# ESPF.net
KiCad netlist of a schematic drawn in EAGLE
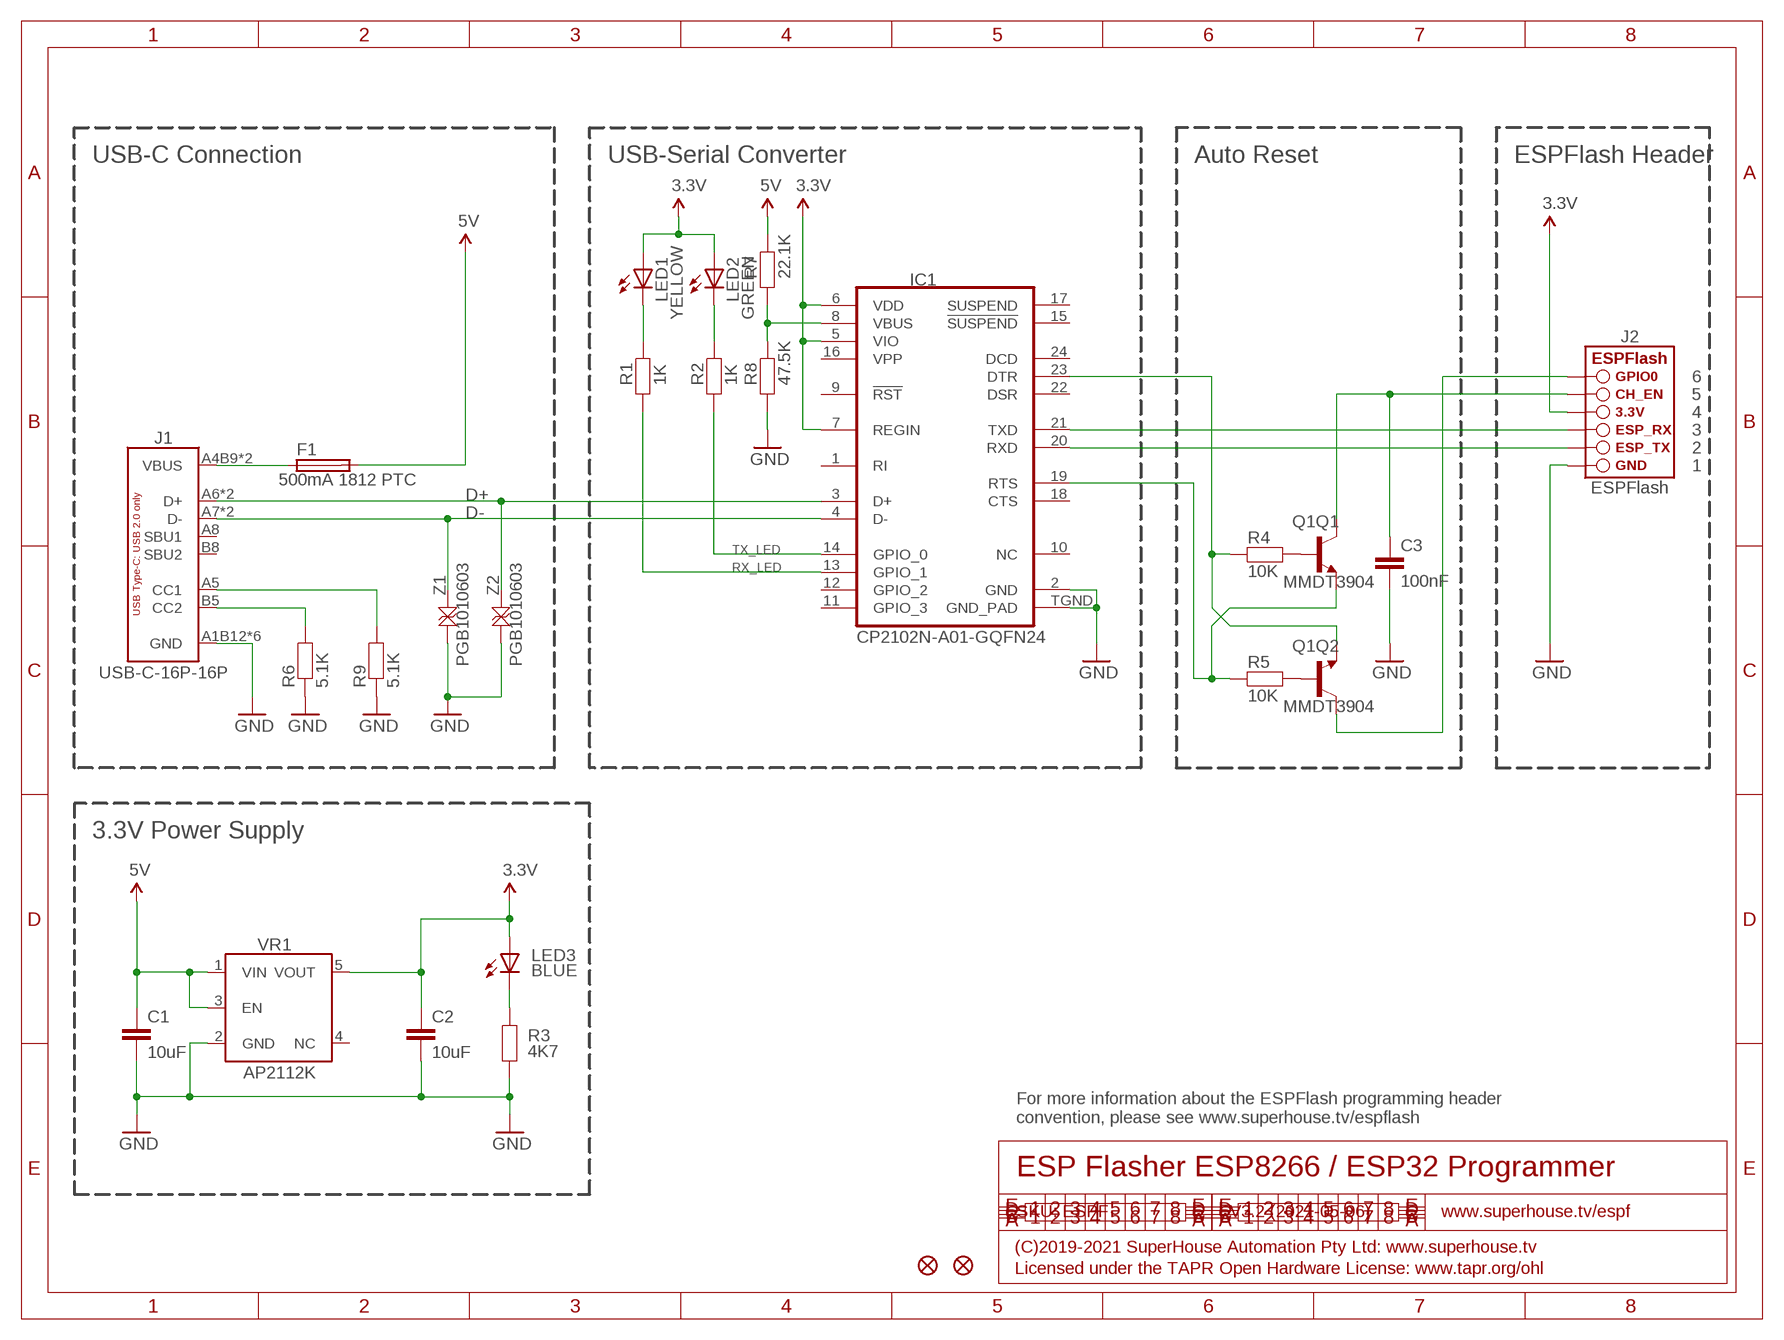
[diagram p0: schematic, sheet 1]

(export (version "E")
  (design (tool "Eeschema 10.0.6"))
  (components
    (comp (ref "C1")
      (value "10uF")
      (footprint "eagle-import:C0603")
      (libsource (lib "eagle-import") (part "CAP0603"))
    )
    (comp (ref "C2")
      (value "10uF")
      (footprint "eagle-import:C0603")
      (libsource (lib "eagle-import") (part "CAP0603"))
    )
    (comp (ref "C3")
      (value "100nF")
      (footprint "eagle-import:C0603")
      (libsource (lib "eagle-import") (part "CAP0603"))
    )
    (comp (ref "F1")
      (value "500mA 1812 PTC")
      (footprint "eagle-import:1812")
      (libsource (lib "eagle-import") (part "PTC050"))
    )
    (comp (ref "FID1")
      (value "FIDUCIAL1X2.5")
      (footprint "eagle-import:FIDUCIAL-1X2.5")
      (libsource (lib "eagle-import") (part "FIDUCIAL1X2.5"))
    )
    (comp (ref "FID2")
      (value "FIDUCIAL1X2.5")
      (footprint "eagle-import:FIDUCIAL-1X2.5")
      (libsource (lib "eagle-import") (part "FIDUCIAL1X2.5"))
    )
    (comp (ref "IC1")
      (value "CP2102N-A01-GQFN24")
      (footprint "eagle-import:QFN-24")
      (libsource (lib "eagle-import") (part "CP2104"))
    )
    (comp (ref "J1")
      (value "USB-C-16P-16P")
      (footprint "eagle-import:USB-C-16P")
      (libsource (lib "eagle-import") (part "USB-C-16P-16P"))
    )
    (comp (ref "J2")
      (value "ESPFLASH-1X6-2.54-PINS-RA")
      (footprint "eagle-import:1X6-2.54-PINS-RA")
      (libsource (lib "eagle-import") (part "ESPFLASH-1X6-2.54-PINS-RA"))
    )
    (comp (ref "LED1")
      (value "YELLOW")
      (footprint "eagle-import:LED-0603")
      (libsource (lib "eagle-import") (part "LED0603"))
    )
    (comp (ref "LED2")
      (value "GREEN")
      (footprint "eagle-import:LED-0603")
      (libsource (lib "eagle-import") (part "LED0603"))
    )
    (comp (ref "LED3")
      (value "BLUE")
      (footprint "eagle-import:LED-0603")
      (libsource (lib "eagle-import") (part "LED0603"))
    )
    (comp (ref "Q1")
      (value "MMDT3904")
      (footprint "eagle-import:SOT-363")
      (libsource (lib "eagle-import") (part "TRANS_NPN_DUAL-MMDT3904"))
    )
    (comp (ref "R1")
      (value "1K")
      (footprint "eagle-import:R0603")
      (libsource (lib "eagle-import") (part "RESISTOR0603"))
    )
    (comp (ref "R2")
      (value "1K")
      (footprint "eagle-import:R0603")
      (libsource (lib "eagle-import") (part "RESISTOR0603"))
    )
    (comp (ref "R3")
      (value "4K7")
      (footprint "eagle-import:R0603")
      (libsource (lib "eagle-import") (part "RESISTOR0603"))
    )
    (comp (ref "R4")
      (value "10K")
      (footprint "eagle-import:R0603")
      (libsource (lib "eagle-import") (part "RESISTOR0603"))
    )
    (comp (ref "R5")
      (value "10K")
      (footprint "eagle-import:R0603")
      (libsource (lib "eagle-import") (part "RESISTOR0603"))
    )
    (comp (ref "R6")
      (value "5.1K")
      (footprint "eagle-import:R0603")
      (libsource (lib "eagle-import") (part "RESISTOR0603"))
    )
    (comp (ref "R7")
      (value "22.1K")
      (footprint "eagle-import:R0603")
      (libsource (lib "eagle-import") (part "RESISTOR0603"))
    )
    (comp (ref "R8")
      (value "47.5K")
      (footprint "eagle-import:R0603")
      (libsource (lib "eagle-import") (part "RESISTOR0603"))
    )
    (comp (ref "R9")
      (value "5.1K")
      (footprint "eagle-import:R0603")
      (libsource (lib "eagle-import") (part "RESISTOR0603"))
    )
    (comp (ref "VR1")
      (value "AP2112K-3.3")
      (footprint "eagle-import:SOT23-5")
      (libsource (lib "eagle-import") (part "AP2112KSOT25"))
    )
    (comp (ref "Z1")
      (value "PGB1010603")
      (footprint "eagle-import:TVS0603")
      (libsource (lib "eagle-import") (part "TVS0603"))
    )
    (comp (ref "Z2")
      (value "PGB1010603")
      (footprint "eagle-import:TVS0603")
      (libsource (lib "eagle-import") (part "TVS0603"))
    )
  )
  (nets
    (net (code "1") (name "/D+") (class "Default")
      (node (ref "IC1") (pin "3") (pinfunction "D+_3") (pintype "bidirectional"))
      (node (ref "J1") (pin "A6") (pinfunction "D+_A6") (pintype "bidirectional"))
      (node (ref "J1") (pin "B6") (pinfunction "D+_B6") (pintype "bidirectional"))
      (node (ref "Z2") (pin "2") (pinfunction "2_2") (pintype "passive"))
    )
    (net (code "2") (name "/D-") (class "Default")
      (node (ref "IC1") (pin "4") (pinfunction "D-_4") (pintype "bidirectional"))
      (node (ref "J1") (pin "A7") (pinfunction "D-_A7") (pintype "bidirectional"))
      (node (ref "J1") (pin "B7") (pinfunction "D-_B7") (pintype "bidirectional"))
      (node (ref "Z1") (pin "2") (pinfunction "2_2") (pintype "passive"))
    )
    (net (code "3") (name "/RX_LED") (class "Default")
      (node (ref "IC1") (pin "13") (pinfunction "GPIO_1_13") (pintype "bidirectional"))
      (node (ref "R1") (pin "1") (pinfunction "1_1") (pintype "passive"))
    )
    (net (code "4") (name "/TX_LED") (class "Default")
      (node (ref "IC1") (pin "14") (pinfunction "GPIO_0_14") (pintype "bidirectional"))
      (node (ref "R2") (pin "1") (pinfunction "1_1") (pintype "passive"))
    )
    (net (code "5") (name "3.3V") (class "Default")
      (node (ref "C2") (pin "1") (pinfunction "1_1") (pintype "passive"))
      (node (ref "IC1") (pin "5") (pinfunction "VIO_5") (pintype "bidirectional"))
      (node (ref "IC1") (pin "6") (pinfunction "VDD_6") (pintype "power_in"))
      (node (ref "IC1") (pin "7") (pinfunction "REGIN_7") (pintype "power_in"))
      (node (ref "J2") (pin "4") (pinfunction "3.3V_4") (pintype "passive"))
      (node (ref "LED1") (pin "A") (pinfunction "A_A") (pintype "passive"))
      (node (ref "LED2") (pin "A") (pinfunction "A_A") (pintype "passive"))
      (node (ref "LED3") (pin "A") (pinfunction "A_A") (pintype "passive"))
      (node (ref "VR1") (pin "5") (pinfunction "VOUT_5") (pintype "bidirectional"))
    )
    (net (code "6") (name "5V") (class "Default")
      (node (ref "C1") (pin "1") (pinfunction "1_1") (pintype "passive"))
      (node (ref "F1") (pin "2") (pinfunction "2_2") (pintype "passive"))
      (node (ref "R7") (pin "2") (pinfunction "2_2") (pintype "passive"))
      (node (ref "VR1") (pin "1") (pinfunction "VIN_1") (pintype "bidirectional"))
      (node (ref "VR1") (pin "3") (pinfunction "EN_3") (pintype "bidirectional"))
    )
    (net (code "7") (name "GND") (class "Default")
      (node (ref "C1") (pin "2") (pinfunction "2_2") (pintype "passive"))
      (node (ref "C2") (pin "2") (pinfunction "2_2") (pintype "passive"))
      (node (ref "C3") (pin "2") (pinfunction "2_2") (pintype "passive"))
      (node (ref "IC1") (pin "2") (pinfunction "GND_2") (pintype "power_in"))
      (node (ref "IC1") (pin "TGND") (pinfunction "GND_PAD_TGND") (pintype "power_in"))
      (node (ref "J1") (pin "A12B1") (pinfunction "GND_A12B1") (pintype "power_in"))
      (node (ref "J1") (pin "A1B12") (pinfunction "GND_A1B12") (pintype "power_in"))
      (node (ref "J1") (pin "FIX1") (pinfunction "GND_FIX1") (pintype "power_in"))
      (node (ref "J1") (pin "FIX2") (pinfunction "GND_FIX2") (pintype "power_in"))
      (node (ref "J1") (pin "FIX3") (pinfunction "GND_FIX3") (pintype "power_in"))
      (node (ref "J1") (pin "FIX4") (pinfunction "GND_FIX4") (pintype "power_in"))
      (node (ref "J2") (pin "1") (pinfunction "GND_1") (pintype "passive"))
      (node (ref "R3") (pin "1") (pinfunction "1_1") (pintype "passive"))
      (node (ref "R6") (pin "1") (pinfunction "1_1") (pintype "passive"))
      (node (ref "R8") (pin "1") (pinfunction "1_1") (pintype "passive"))
      (node (ref "R9") (pin "1") (pinfunction "1_1") (pintype "passive"))
      (node (ref "VR1") (pin "2") (pinfunction "GND_2") (pintype "bidirectional"))
      (node (ref "Z1") (pin "1") (pinfunction "1_1") (pintype "passive"))
      (node (ref "Z2") (pin "1") (pinfunction "1_1") (pintype "passive"))
    )
    (net (code "8") (name "Net-(F1-Pad1)") (class "Default")
      (node (ref "F1") (pin "1") (pinfunction "1_1") (pintype "passive"))
      (node (ref "J1") (pin "A4B9") (pinfunction "VBUS_A4B9") (pintype "power_in"))
      (node (ref "J1") (pin "A9B4") (pinfunction "VBUS_A9B4") (pintype "power_in"))
    )
    (net (code "9") (name "Net-(IC1-DTR)") (class "Default")
      (node (ref "IC1") (pin "23") (pinfunction "DTR_23") (pintype "output"))
      (node (ref "Q1") (pin "1") (pinfunction "E_1") (pintype "passive"))
      (node (ref "R4") (pin "1") (pinfunction "1_1") (pintype "passive"))
    )
    (net (code "10") (name "Net-(IC1-RTS)") (class "Default")
      (node (ref "IC1") (pin "19") (pinfunction "RTS_19") (pintype "output"))
      (node (ref "Q1") (pin "4") (pinfunction "E_4") (pintype "passive"))
      (node (ref "R5") (pin "1") (pinfunction "1_1") (pintype "passive"))
    )
    (net (code "11") (name "Net-(IC1-RXD)") (class "Default")
      (node (ref "IC1") (pin "20") (pinfunction "RXD_20") (pintype "input"))
      (node (ref "J2") (pin "2") (pinfunction "ESP_TX_2") (pintype "passive"))
    )
    (net (code "12") (name "Net-(IC1-TXD)") (class "Default")
      (node (ref "IC1") (pin "21") (pinfunction "TXD_21") (pintype "output"))
      (node (ref "J2") (pin "3") (pinfunction "ESP_RX_3") (pintype "passive"))
    )
    (net (code "13") (name "Net-(IC1-VBUS)") (class "Default")
      (node (ref "IC1") (pin "8") (pinfunction "VBUS_8") (pintype "bidirectional"))
      (node (ref "R7") (pin "1") (pinfunction "1_1") (pintype "passive"))
      (node (ref "R8") (pin "2") (pinfunction "2_2") (pintype "passive"))
    )
    (net (code "14") (name "Net-(J1-CC1)") (class "Default")
      (node (ref "J1") (pin "A5") (pinfunction "CC1_A5") (pintype "bidirectional"))
      (node (ref "R9") (pin "2") (pinfunction "2_2") (pintype "passive"))
    )
    (net (code "15") (name "Net-(J1-CC2)") (class "Default")
      (node (ref "J1") (pin "B5") (pinfunction "CC2_B5") (pintype "bidirectional"))
      (node (ref "R6") (pin "2") (pinfunction "2_2") (pintype "passive"))
    )
    (net (code "16") (name "Net-(J2-CH_EN)") (class "Default")
      (node (ref "C3") (pin "1") (pinfunction "1_1") (pintype "passive"))
      (node (ref "J2") (pin "5") (pinfunction "CH_EN_5") (pintype "passive"))
      (node (ref "Q1") (pin "3") (pinfunction "C_3") (pintype "passive"))
    )
    (net (code "17") (name "Net-(J2-GPIO0)") (class "Default")
      (node (ref "J2") (pin "6") (pinfunction "GPIO0_6") (pintype "passive"))
      (node (ref "Q1") (pin "6") (pinfunction "C_6") (pintype "passive"))
    )
    (net (code "18") (name "Net-(LED1-PadC)") (class "Default")
      (node (ref "LED1") (pin "C") (pinfunction "C_C") (pintype "passive"))
      (node (ref "R1") (pin "2") (pinfunction "2_2") (pintype "passive"))
    )
    (net (code "19") (name "Net-(LED2-PadC)") (class "Default")
      (node (ref "LED2") (pin "C") (pinfunction "C_C") (pintype "passive"))
      (node (ref "R2") (pin "2") (pinfunction "2_2") (pintype "passive"))
    )
    (net (code "20") (name "Net-(LED3-PadC)") (class "Default")
      (node (ref "LED3") (pin "C") (pinfunction "C_C") (pintype "passive"))
      (node (ref "R3") (pin "2") (pinfunction "2_2") (pintype "passive"))
    )
    (net (code "21") (name "Net-(Q1A-B)") (class "Default")
      (node (ref "Q1") (pin "5") (pinfunction "B_5") (pintype "passive"))
      (node (ref "R4") (pin "2") (pinfunction "2_2") (pintype "passive"))
    )
    (net (code "22") (name "Net-(Q1B-B)") (class "Default")
      (node (ref "Q1") (pin "2") (pinfunction "B_2") (pintype "passive"))
      (node (ref "R5") (pin "2") (pinfunction "2_2") (pintype "passive"))
    )
    (net (code "23") (name "unconnected-(IC1-CTS-Pad18)") (class "Default")
      (node (ref "IC1") (pin "18") (pinfunction "CTS_18") (pintype "input"))
    )
    (net (code "24") (name "unconnected-(IC1-DCD-Pad24)") (class "Default")
      (node (ref "IC1") (pin "24") (pinfunction "DCD_24") (pintype "input"))
    )
    (net (code "25") (name "unconnected-(IC1-DSR-Pad22)") (class "Default")
      (node (ref "IC1") (pin "22") (pinfunction "DSR_22") (pintype "input"))
    )
    (net (code "26") (name "unconnected-(IC1-GPIO_2-Pad12)") (class "Default")
      (node (ref "IC1") (pin "12") (pinfunction "GPIO_2_12") (pintype "bidirectional"))
    )
    (net (code "27") (name "unconnected-(IC1-GPIO_3-Pad11)") (class "Default")
      (node (ref "IC1") (pin "11") (pinfunction "GPIO_3_11") (pintype "bidirectional"))
    )
    (net (code "28") (name "unconnected-(IC1-NC-Pad10)") (class "Default")
      (node (ref "IC1") (pin "10") (pinfunction "NC_10") (pintype "input"))
    )
    (net (code "29") (name "unconnected-(IC1-RI-Pad1)") (class "Default")
      (node (ref "IC1") (pin "1") (pinfunction "RI_1") (pintype "input"))
    )
    (net (code "30") (name "unconnected-(IC1-SUSPEND-Pad17)") (class "Default")
      (node (ref "IC1") (pin "17") (pinfunction "SUSPEND_17") (pintype "output"))
    )
    (net (code "31") (name "unconnected-(IC1-VPP-Pad16)") (class "Default")
      (node (ref "IC1") (pin "16") (pinfunction "VPP_16") (pintype "bidirectional"))
    )
    (net (code "32") (name "unconnected-(IC1-~{RST}-Pad9)") (class "Default")
      (node (ref "IC1") (pin "9") (pinfunction "~{RST}_9") (pintype "bidirectional"))
    )
    (net (code "33") (name "unconnected-(IC1-~{SUSPEND}-Pad15)") (class "Default")
      (node (ref "IC1") (pin "15") (pinfunction "~{SUSPEND}_15") (pintype "output"))
    )
    (net (code "34") (name "unconnected-(J1-SBU1-PadA8)") (class "Default")
      (node (ref "J1") (pin "A8") (pinfunction "SBU1_A8") (pintype "bidirectional"))
    )
    (net (code "35") (name "unconnected-(J1-SBU2-PadB8)") (class "Default")
      (node (ref "J1") (pin "B8") (pinfunction "SBU2_B8") (pintype "bidirectional"))
    )
    (net (code "36") (name "unconnected-(VR1-NC-Pad4)") (class "Default")
      (node (ref "VR1") (pin "4") (pinfunction "NC_4") (pintype "bidirectional"))
    )
  )
)
